# EarBones.net
KiCad netlist of a schematic drawn in EAGLE
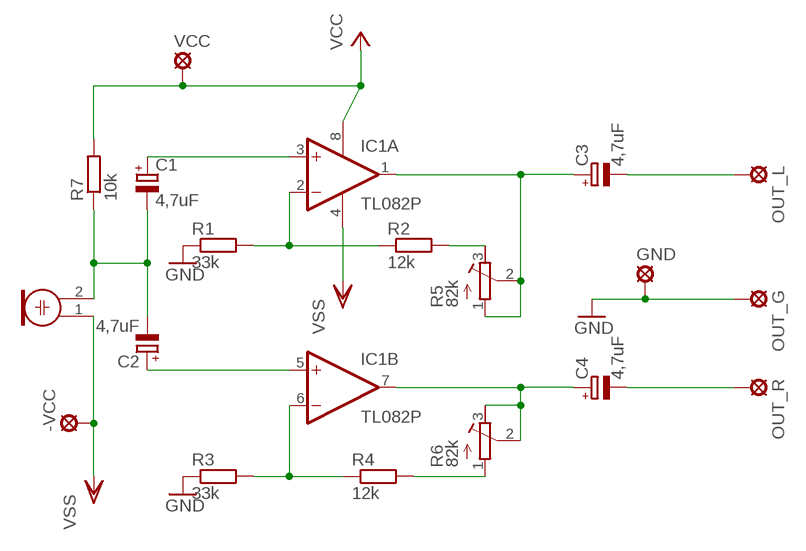
[diagram p0: schematic, sheet 1]

(export (version "E")
  (design (tool "Eeschema 10.0.6"))
  (components
    (comp (ref "-VCC")
      (value "LSP10")
      (footprint "eagle-import:LSP10")
      (libsource (lib "eagle-import") (part "LSP10"))
    )
    (comp (ref "C1")
      (value "4,7uF")
      (footprint "eagle-import:E2,5-6E")
      (libsource (lib "eagle-import") (part "CPOL-EUE2,5-6E"))
    )
    (comp (ref "C2")
      (value "4,7uF")
      (footprint "eagle-import:E2,5-6E")
      (libsource (lib "eagle-import") (part "CPOL-EUE2,5-6E"))
    )
    (comp (ref "C3")
      (value "4,7uF")
      (footprint "eagle-import:E2,5-6E")
      (libsource (lib "eagle-import") (part "CPOL-EUE2,5-6E"))
    )
    (comp (ref "C4")
      (value "4,7uF")
      (footprint "eagle-import:E2,5-6E")
      (libsource (lib "eagle-import") (part "CPOL-EUE2,5-6E"))
    )
    (comp (ref "GND")
      (value "LSP10")
      (footprint "eagle-import:LSP10")
      (libsource (lib "eagle-import") (part "LSP10"))
    )
    (comp (ref "IC1")
      (value "TL082P")
      (footprint "eagle-import:DIL08")
      (libsource (lib "eagle-import") (part "TL082P"))
    )
    (comp (ref "M1")
      (value "ELECTRET_MICROPHON-WM-61B")
      (footprint "eagle-import:WM-61B")
      (libsource (lib "eagle-import") (part "ELECTRET_MICROPHON-WM-61B"))
    )
    (comp (ref "OUT_G")
      (value "LSP10")
      (footprint "eagle-import:LSP10")
      (libsource (lib "eagle-import") (part "LSP10"))
    )
    (comp (ref "OUT_L")
      (value "LSP10")
      (footprint "eagle-import:LSP10")
      (libsource (lib "eagle-import") (part "LSP10"))
    )
    (comp (ref "OUT_R")
      (value "LSP10")
      (footprint "eagle-import:LSP10")
      (libsource (lib "eagle-import") (part "LSP10"))
    )
    (comp (ref "R1")
      (value "33k")
      (footprint "eagle-import:0207_10")
      (libsource (lib "eagle-import") (part "R-EU_0207/10"))
    )
    (comp (ref "R2")
      (value "12k")
      (footprint "eagle-import:0207_10")
      (libsource (lib "eagle-import") (part "R-EU_0207/10"))
    )
    (comp (ref "R3")
      (value "33k")
      (footprint "eagle-import:0207_10")
      (libsource (lib "eagle-import") (part "R-EU_0207/10"))
    )
    (comp (ref "R4")
      (value "12k")
      (footprint "eagle-import:0207_10")
      (libsource (lib "eagle-import") (part "R-EU_0207/10"))
    )
    (comp (ref "R5")
      (value "82k")
      (footprint "eagle-import:RTRIM3339P")
      (libsource (lib "eagle-import") (part "R-TRIMM3339P"))
    )
    (comp (ref "R6")
      (value "82k")
      (footprint "eagle-import:RTRIM3339P")
      (libsource (lib "eagle-import") (part "R-TRIMM3339P"))
    )
    (comp (ref "R7")
      (value "10k")
      (footprint "eagle-import:0207_10")
      (libsource (lib "eagle-import") (part "R-EU_0207/10"))
    )
    (comp (ref "VCC")
      (value "LSP10")
      (footprint "eagle-import:LSP10")
      (libsource (lib "eagle-import") (part "LSP10"))
    )
  )
  (nets
    (net (code "1") (name "GND") (class "Default")
      (node (ref "GND") (pin "MP") (pinfunction "MP_MP") (pintype "passive"))
      (node (ref "OUT_G") (pin "MP") (pinfunction "MP_MP") (pintype "passive"))
      (node (ref "R1") (pin "1") (pinfunction "1_1") (pintype "passive"))
      (node (ref "R3") (pin "1") (pinfunction "1_1") (pintype "passive"))
    )
    (net (code "2") (name "Net-(C1-Pad-)") (class "Default")
      (node (ref "C1") (pin "-") (pinfunction "-_-") (pintype "passive"))
      (node (ref "C2") (pin "-") (pinfunction "-_-") (pintype "passive"))
      (node (ref "M1") (pin "2") (pinfunction "2_2") (pintype "passive"))
      (node (ref "R7") (pin "1") (pinfunction "1_1") (pintype "passive"))
    )
    (net (code "3") (name "Net-(C3-Pad-)") (class "Default")
      (node (ref "C3") (pin "-") (pinfunction "-_-") (pintype "passive"))
      (node (ref "OUT_L") (pin "MP") (pinfunction "MP_MP") (pintype "passive"))
    )
    (net (code "4") (name "Net-(C4-Pad-)") (class "Default")
      (node (ref "C4") (pin "-") (pinfunction "-_-") (pintype "passive"))
      (node (ref "OUT_R") (pin "MP") (pinfunction "MP_MP") (pintype "passive"))
    )
    (net (code "5") (name "Net-(IC1A-+IN)") (class "Default")
      (node (ref "C1") (pin "+") (pinfunction "+_+") (pintype "passive"))
      (node (ref "IC1") (pin "3") (pinfunction "+IN_3") (pintype "input"))
    )
    (net (code "6") (name "Net-(IC1A--IN)") (class "Default")
      (node (ref "IC1") (pin "2") (pinfunction "-IN_2") (pintype "input"))
      (node (ref "R1") (pin "2") (pinfunction "2_2") (pintype "passive"))
      (node (ref "R2") (pin "1") (pinfunction "1_1") (pintype "passive"))
    )
    (net (code "7") (name "Net-(IC1A-OUT)") (class "Default")
      (node (ref "C3") (pin "+") (pinfunction "+_+") (pintype "passive"))
      (node (ref "IC1") (pin "1") (pinfunction "OUT_1") (pintype "output"))
      (node (ref "R5") (pin "1") (pinfunction "A_1") (pintype "passive"))
      (node (ref "R5") (pin "2") (pinfunction "S_2") (pintype "passive"))
    )
    (net (code "8") (name "Net-(IC1B-+IN)") (class "Default")
      (node (ref "C2") (pin "+") (pinfunction "+_+") (pintype "passive"))
      (node (ref "IC1") (pin "5") (pinfunction "+IN_5") (pintype "input"))
    )
    (net (code "9") (name "Net-(IC1B--IN)") (class "Default")
      (node (ref "IC1") (pin "6") (pinfunction "-IN_6") (pintype "input"))
      (node (ref "R3") (pin "2") (pinfunction "2_2") (pintype "passive"))
      (node (ref "R4") (pin "1") (pinfunction "1_1") (pintype "passive"))
    )
    (net (code "10") (name "Net-(IC1B-OUT)") (class "Default")
      (node (ref "C4") (pin "+") (pinfunction "+_+") (pintype "passive"))
      (node (ref "IC1") (pin "7") (pinfunction "OUT_7") (pintype "output"))
      (node (ref "R6") (pin "2") (pinfunction "S_2") (pintype "passive"))
      (node (ref "R6") (pin "3") (pinfunction "E_3") (pintype "passive"))
    )
    (net (code "11") (name "Net-(R5-E)") (class "Default")
      (node (ref "R2") (pin "2") (pinfunction "2_2") (pintype "passive"))
      (node (ref "R5") (pin "3") (pinfunction "E_3") (pintype "passive"))
    )
    (net (code "12") (name "Net-(R6-A)") (class "Default")
      (node (ref "R4") (pin "2") (pinfunction "2_2") (pintype "passive"))
      (node (ref "R6") (pin "1") (pinfunction "A_1") (pintype "passive"))
    )
    (net (code "13") (name "VCC") (class "Default")
      (node (ref "IC1") (pin "8") (pinfunction "V+_8") (pintype "power_in"))
      (node (ref "R7") (pin "2") (pinfunction "2_2") (pintype "passive"))
      (node (ref "VCC") (pin "MP") (pinfunction "MP_MP") (pintype "passive"))
    )
    (net (code "14") (name "VSS") (class "Default")
      (node (ref "-VCC") (pin "MP") (pinfunction "MP_MP") (pintype "passive"))
      (node (ref "IC1") (pin "4") (pinfunction "V-_4") (pintype "power_in"))
      (node (ref "M1") (pin "1") (pinfunction "1_1") (pintype "passive"))
    )
  )
)
